# SD.net
KiCad netlist of a schematic drawn in Altium Designer
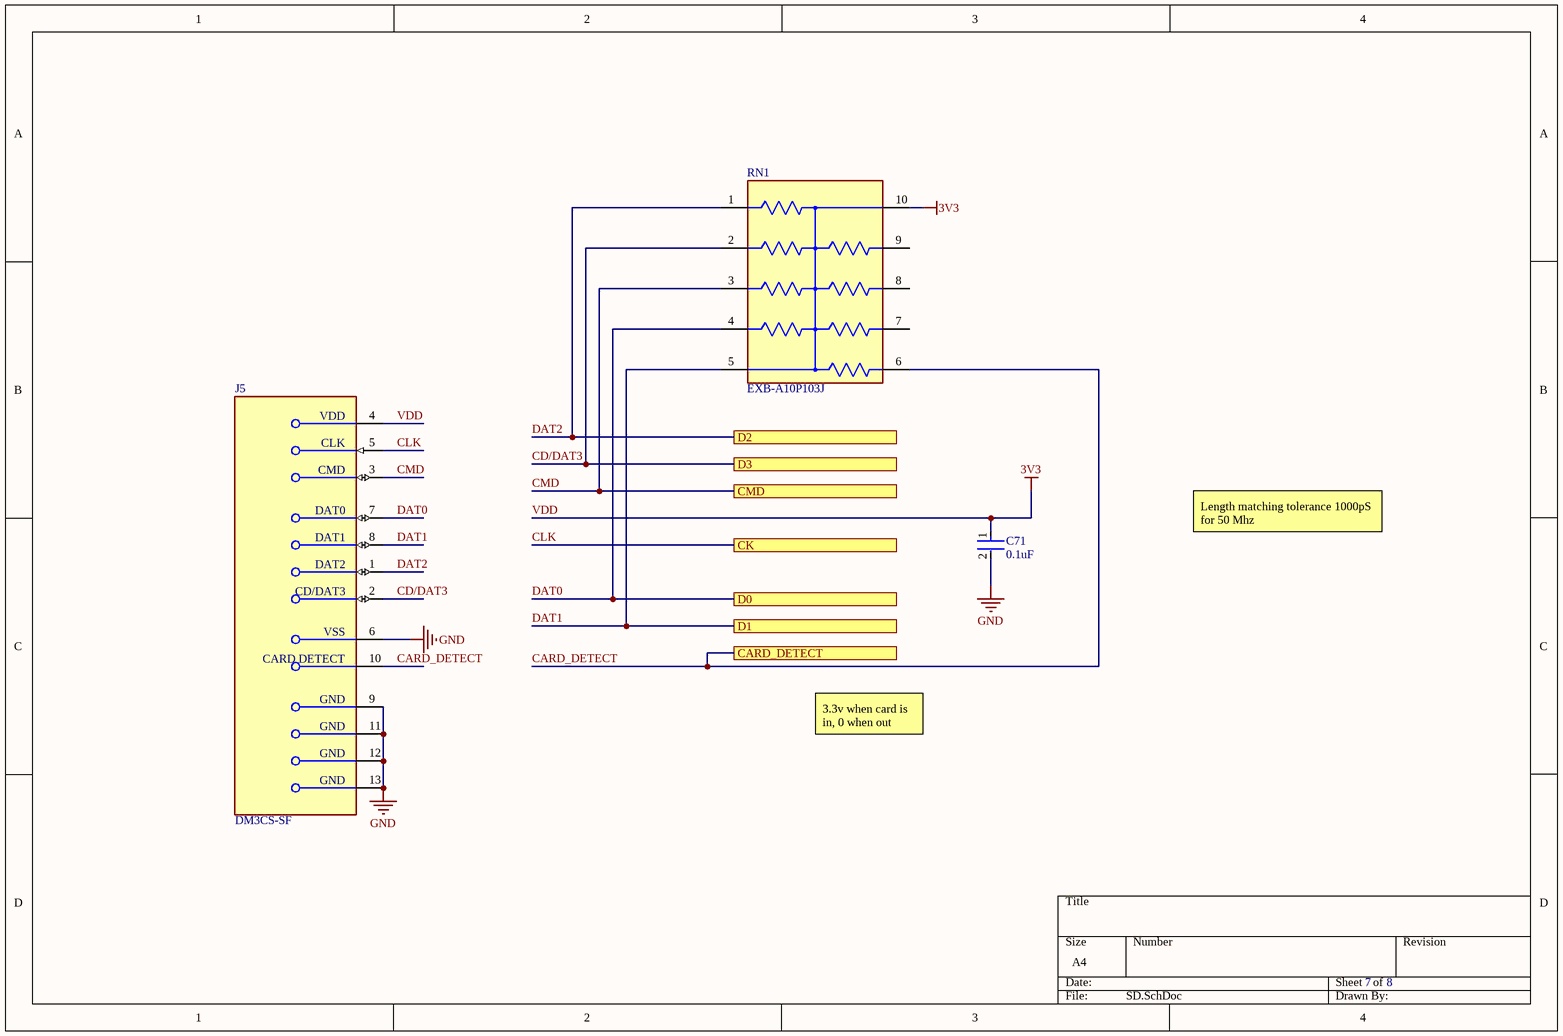
[diagram p0: SD.SchDoc]

(export (version "E")
  (design (tool "Eeschema 10.0.6"))
  (components
    (comp (ref "C71")
      (value "0.1uF")
      (footprint "FP-CL10-IPC_C")
      (description "Cap Ceramic 100nF 16V X7R ±10% Pad SMD 0603 +125°C T/R\r\nCL10B104KO8WPNC")
      (fields (field (name "TOLERANCE") "10%"))
      (libsource (lib "Altium Content Vault") (part "b4654b650e69147ec39a6b967a45e02"))
    )
    (comp (ref "J5")
      (value "DM3CS-SF")
      (footprint "FP-DM3CS-SF-MFG")
      (description "CONN MICRO SD CARD HINGED TYPE")
      (libsource (lib "Altium Content Vault") (part "bac915de5305cfdd1ca301aae530106"))
    )
    (comp (ref "RN1")
      (value "EXB-A10P103J")
      (footprint "FP-EXBA-MFG")
      (fields (field (name "TOLERANCE") "5%"))
      (libsource (lib "Altium Content Vault") (part "6f92e8632ed83f5d70d618d178f1129"))
    )
  )
  (nets
    (net (code "1") (name "/CARD_DETECT") (class "Default")
      (node (ref "J5") (pin "10") (pinfunction "CARD_DETECT_10") (pintype "passive"))
      (node (ref "RN1") (pin "6") (pinfunction "6_6") (pintype "passive"))
    )
    (net (code "2") (name "/CD{slash}DAT3") (class "Default")
      (node (ref "J5") (pin "2") (pinfunction "CD/DAT3_2") (pintype "bidirectional"))
      (node (ref "RN1") (pin "2") (pinfunction "2_2") (pintype "passive"))
    )
    (net (code "3") (name "/CLK") (class "Default")
      (node (ref "J5") (pin "5") (pinfunction "CLK_5") (pintype "input"))
    )
    (net (code "4") (name "/CMD") (class "Default")
      (node (ref "J5") (pin "3") (pinfunction "CMD_3") (pintype "bidirectional"))
      (node (ref "RN1") (pin "3") (pinfunction "3_3") (pintype "passive"))
    )
    (net (code "5") (name "/DAT0") (class "Default")
      (node (ref "J5") (pin "7") (pinfunction "DAT0_7") (pintype "bidirectional"))
      (node (ref "RN1") (pin "4") (pinfunction "4_4") (pintype "passive"))
    )
    (net (code "6") (name "/DAT1") (class "Default")
      (node (ref "J5") (pin "8") (pinfunction "DAT1_8") (pintype "bidirectional"))
      (node (ref "RN1") (pin "5") (pinfunction "5_5") (pintype "passive"))
    )
    (net (code "7") (name "/DAT2") (class "Default")
      (node (ref "J5") (pin "1") (pinfunction "DAT2_1") (pintype "bidirectional"))
      (node (ref "RN1") (pin "1") (pinfunction "1_1") (pintype "passive"))
    )
    (net (code "8") (name "3V3") (class "Default")
      (node (ref "C71") (pin "1") (pinfunction "1_1") (pintype "passive"))
      (node (ref "J5") (pin "4") (pinfunction "VDD_4") (pintype "power_in"))
      (node (ref "RN1") (pin "10") (pinfunction "10_10") (pintype "passive"))
    )
    (net (code "9") (name "GND") (class "Default")
      (node (ref "C71") (pin "2") (pinfunction "2_2") (pintype "passive"))
      (node (ref "J5") (pin "11") (pinfunction "GND_11") (pintype "power_in"))
      (node (ref "J5") (pin "12") (pinfunction "GND_12") (pintype "power_in"))
      (node (ref "J5") (pin "13") (pinfunction "GND_13") (pintype "power_in"))
      (node (ref "J5") (pin "6") (pinfunction "VSS_6") (pintype "power_in"))
      (node (ref "J5") (pin "9") (pinfunction "GND_9") (pintype "power_in"))
    )
    (net (code "10") (name "unconnected-(RN1-Pad7)") (class "Default")
      (node (ref "RN1") (pin "7") (pinfunction "7_7") (pintype "passive"))
    )
    (net (code "11") (name "unconnected-(RN1-Pad8)") (class "Default")
      (node (ref "RN1") (pin "8") (pinfunction "8_8") (pintype "passive"))
    )
    (net (code "12") (name "unconnected-(RN1-Pad9)") (class "Default")
      (node (ref "RN1") (pin "9") (pinfunction "9_9") (pintype "passive"))
    )
  )
)
